# 250_redraw.net
KiCad netlist of a schematic drawn in EAGLE
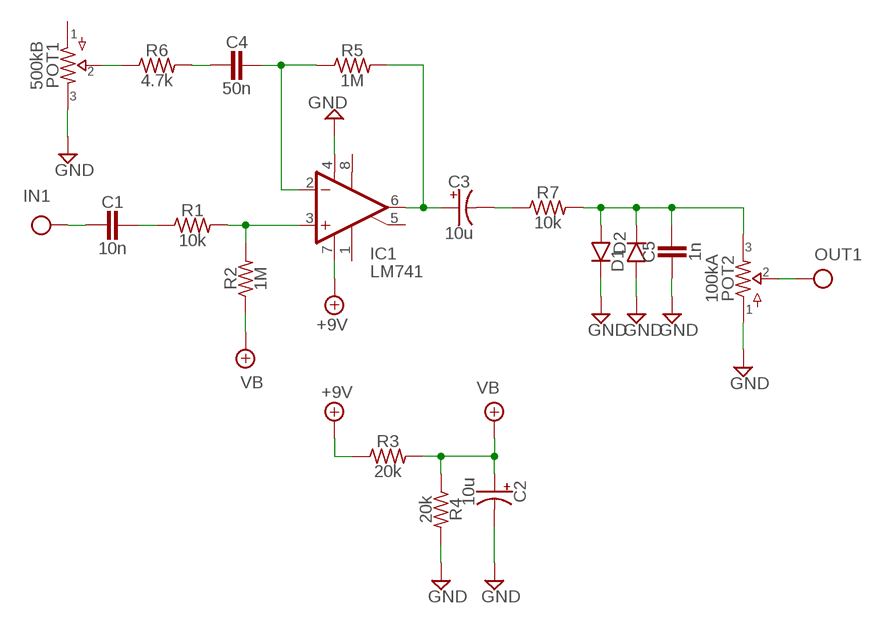
[diagram p0: schematic, sheet 1]

(export (version "E")
  (design (tool "Eeschema 10.0.6"))
  (components
    (comp (ref "C1")
      (value "10n")
      (footprint "eagle-import:BOX_SMALL")
      (libsource (lib "eagle-import") (part "CER/FILMBOX.1"))
    )
    (comp (ref "C2")
      (value "10u")
      (footprint "eagle-import:050_020")
      (libsource (lib "eagle-import") (part "0500"))
    )
    (comp (ref "C3")
      (value "10u")
      (footprint "eagle-import:050_020")
      (libsource (lib "eagle-import") (part "0500"))
    )
    (comp (ref "C4")
      (value "50n")
      (footprint "eagle-import:BOX_SMALL")
      (libsource (lib "eagle-import") (part "CER/FILMBOX.1"))
    )
    (comp (ref "C5")
      (value "1n")
      (footprint "eagle-import:BOX_SMALL")
      (libsource (lib "eagle-import") (part "CER/FILMBOX.1"))
    )
    (comp (ref "D1")
      (value "DO35.2")
      (footprint "eagle-import:DO35-2")
      (libsource (lib "eagle-import") (part "DO35.2"))
    )
    (comp (ref "D2")
      (value "DO35.2")
      (footprint "eagle-import:DO35-2")
      (libsource (lib "eagle-import") (part "DO35.2"))
    )
    (comp (ref "IC1")
      (value "LM741")
      (footprint "eagle-import:DIL0")
      (libsource (lib "eagle-import") (part "SINGLETH"))
    )
    (comp (ref "POT1")
      (value "500kB")
      (footprint "eagle-import:16MM")
      (libsource (lib "eagle-import") (part "POTS16MM"))
    )
    (comp (ref "POT2")
      (value "100kA")
      (footprint "eagle-import:16MM")
      (libsource (lib "eagle-import") (part "POTS16MM"))
    )
    (comp (ref "R1")
      (value "10k")
      (footprint "eagle-import:R0207_3")
      (libsource (lib "eagle-import") (part "R_.3B"))
    )
    (comp (ref "R2")
      (value "1M")
      (footprint "eagle-import:R0207_3")
      (libsource (lib "eagle-import") (part "R_.3B"))
    )
    (comp (ref "R3")
      (value "20k")
      (footprint "eagle-import:R0207_3")
      (libsource (lib "eagle-import") (part "R_.3B"))
    )
    (comp (ref "R4")
      (value "20k")
      (footprint "eagle-import:R0207_3")
      (libsource (lib "eagle-import") (part "R_.3B"))
    )
    (comp (ref "R5")
      (value "1M")
      (footprint "eagle-import:R0207_3")
      (libsource (lib "eagle-import") (part "R_.3B"))
    )
    (comp (ref "R6")
      (value "4.7k")
      (footprint "eagle-import:R0207_3")
      (libsource (lib "eagle-import") (part "R_.3B"))
    )
    (comp (ref "R7")
      (value "10k")
      (footprint "eagle-import:R0207_3")
      (libsource (lib "eagle-import") (part "R_.3B"))
    )
  )
  (nets
    (net (code "1") (name "+9V") (class "Default")
      (node (ref "IC1") (pin "7") (pinfunction "V+_7") (pintype "power_in"))
      (node (ref "R3") (pin "1") (pinfunction "1_1") (pintype "passive"))
    )
    (net (code "2") (name "GND") (class "Default")
      (node (ref "C2") (pin "-") (pinfunction "-_-") (pintype "passive"))
      (node (ref "C5") (pin "2") (pinfunction "2_2") (pintype "passive"))
      (node (ref "D1") (pin "C") (pinfunction "C_C") (pintype "passive"))
      (node (ref "D2") (pin "A") (pinfunction "A_A") (pintype "passive"))
      (node (ref "IC1") (pin "4") (pinfunction "V-_4") (pintype "power_in"))
      (node (ref "POT1") (pin "3") (pinfunction "3_3") (pintype "passive"))
      (node (ref "POT2") (pin "1") (pinfunction "1_1") (pintype "passive"))
      (node (ref "R4") (pin "2") (pinfunction "2_2") (pintype "passive"))
    )
    (net (code "3") (name "IN") (class "Default")
      (node (ref "C1") (pin "2") (pinfunction "2_2") (pintype "passive"))
    )
    (net (code "4") (name "Net-(C1-Pad1)") (class "Default")
      (node (ref "C1") (pin "1") (pinfunction "1_1") (pintype "passive"))
      (node (ref "R1") (pin "1") (pinfunction "1_1") (pintype "passive"))
    )
    (net (code "5") (name "Net-(C3-Pad-)") (class "Default")
      (node (ref "C3") (pin "-") (pinfunction "-_-") (pintype "passive"))
      (node (ref "R7") (pin "1") (pinfunction "1_1") (pintype "passive"))
    )
    (net (code "6") (name "Net-(C4-Pad2)") (class "Default")
      (node (ref "C4") (pin "2") (pinfunction "2_2") (pintype "passive"))
      (node (ref "R6") (pin "2") (pinfunction "2_2") (pintype "passive"))
    )
    (net (code "7") (name "Net-(C5-Pad1)") (class "Default")
      (node (ref "C5") (pin "1") (pinfunction "1_1") (pintype "passive"))
      (node (ref "D1") (pin "A") (pinfunction "A_A") (pintype "passive"))
      (node (ref "D2") (pin "C") (pinfunction "C_C") (pintype "passive"))
      (node (ref "POT2") (pin "3") (pinfunction "3_3") (pintype "passive"))
      (node (ref "R7") (pin "2") (pinfunction "2_2") (pintype "passive"))
    )
    (net (code "8") (name "Net-(IC1-+IN)") (class "Default")
      (node (ref "IC1") (pin "3") (pinfunction "+IN_3") (pintype "input"))
      (node (ref "R1") (pin "2") (pinfunction "2_2") (pintype "passive"))
      (node (ref "R2") (pin "2") (pinfunction "2_2") (pintype "passive"))
    )
    (net (code "9") (name "Net-(IC1--IN)") (class "Default")
      (node (ref "C4") (pin "1") (pinfunction "1_1") (pintype "passive"))
      (node (ref "IC1") (pin "2") (pinfunction "-IN_2") (pintype "input"))
      (node (ref "R5") (pin "1") (pinfunction "1_1") (pintype "passive"))
    )
    (net (code "10") (name "Net-(IC1-OUT)") (class "Default")
      (node (ref "C3") (pin "+") (pinfunction "+_+") (pintype "passive"))
      (node (ref "IC1") (pin "6") (pinfunction "OUT_6") (pintype "output"))
      (node (ref "R5") (pin "2") (pinfunction "2_2") (pintype "passive"))
    )
    (net (code "11") (name "Net-(POT1-Pad2)") (class "Default")
      (node (ref "POT1") (pin "2") (pinfunction "2_2") (pintype "passive"))
      (node (ref "R6") (pin "1") (pinfunction "1_1") (pintype "passive"))
    )
    (net (code "12") (name "OUT") (class "Default")
      (node (ref "POT2") (pin "2") (pinfunction "2_2") (pintype "passive"))
    )
    (net (code "13") (name "VB") (class "Default")
      (node (ref "C2") (pin "+") (pinfunction "+_+") (pintype "passive"))
      (node (ref "R2") (pin "1") (pinfunction "1_1") (pintype "passive"))
      (node (ref "R3") (pin "2") (pinfunction "2_2") (pintype "passive"))
      (node (ref "R4") (pin "1") (pinfunction "1_1") (pintype "passive"))
    )
    (net (code "14") (name "unconnected-(IC1-ON1-Pad1)") (class "Default")
      (node (ref "IC1") (pin "1") (pinfunction "ON1_1") (pintype "passive"))
    )
    (net (code "15") (name "unconnected-(IC1-ON2-Pad5)") (class "Default")
      (node (ref "IC1") (pin "5") (pinfunction "ON2_5") (pintype "passive"))
    )
    (net (code "16") (name "unconnected-(IC1-OPT-Pad8)") (class "Default")
      (node (ref "IC1") (pin "8") (pinfunction "OPT_8") (pintype "passive"))
    )
    (net (code "17") (name "unconnected-(POT1-Pad1)") (class "Default")
      (node (ref "POT1") (pin "1") (pinfunction "1_1") (pintype "passive"))
    )
  )
)
